# NRF52_Metal_Detector_v1_0.net
KiCad netlist of a schematic drawn in EAGLE
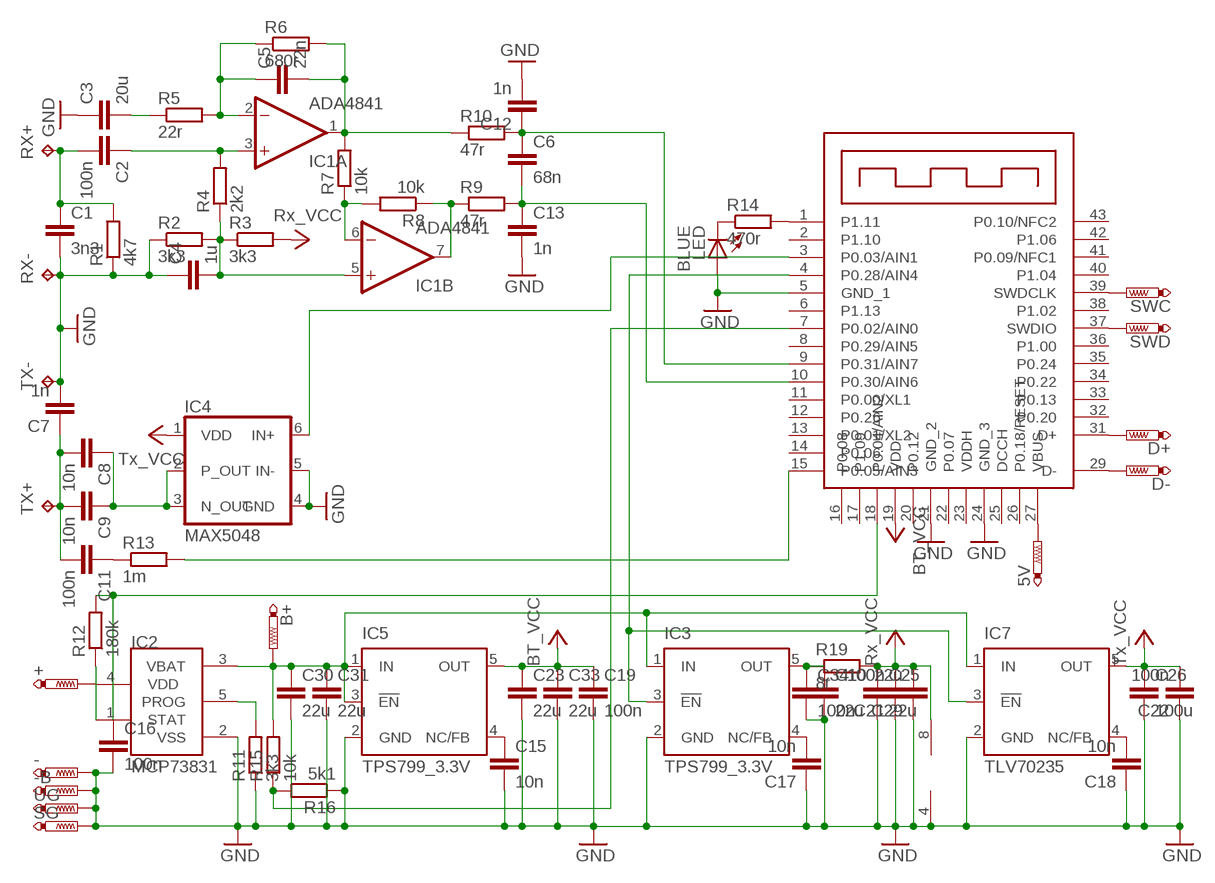
[diagram p0: schematic, sheet 1]

(export (version "E")
  (design (tool "Eeschema 10.0.6"))
  (components
    (comp (ref "+")
      (value "PTR1TP20SQ")
      (footprint "eagle-import:TP20SQ")
      (libsource (lib "eagle-import") (part "PTR1TP20SQ"))
    )
    (comp (ref "-")
      (value "PTR1TP20SQ")
      (footprint "eagle-import:TP20SQ")
      (libsource (lib "eagle-import") (part "PTR1TP20SQ"))
    )
    (comp (ref "-B")
      (value "PTR1TP20SQ")
      (footprint "eagle-import:TP20SQ")
      (libsource (lib "eagle-import") (part "PTR1TP20SQ"))
    )
    (comp (ref "5V")
      (value "PTR1TP13SQ")
      (footprint "eagle-import:TP13SQ")
      (libsource (lib "eagle-import") (part "PTR1TP13SQ"))
    )
    (comp (ref "B+")
      (value "PTR1TP20SQ")
      (footprint "eagle-import:TP20SQ")
      (libsource (lib "eagle-import") (part "PTR1TP20SQ"))
    )
    (comp (ref "C1")
      (value "3n3")
      (footprint "eagle-import:C0805")
      (libsource (lib "eagle-import") (part "C-EUC0805"))
    )
    (comp (ref "C2")
      (value "100n")
      (footprint "eagle-import:C1206")
      (libsource (lib "eagle-import") (part "C-EUC1206"))
    )
    (comp (ref "C3")
      (value "20u")
      (footprint "eagle-import:C1206")
      (libsource (lib "eagle-import") (part "C-EUC1206"))
    )
    (comp (ref "C4")
      (value "1u")
      (footprint "eagle-import:C1206")
      (libsource (lib "eagle-import") (part "C-EUC1206"))
    )
    (comp (ref "C5")
      (value "22n")
      (footprint "eagle-import:C0805")
      (libsource (lib "eagle-import") (part "C-EUC0805"))
    )
    (comp (ref "C6")
      (value "68n")
      (footprint "eagle-import:C1206")
      (libsource (lib "eagle-import") (part "C-EUC1206"))
    )
    (comp (ref "C7")
      (value "1n")
      (footprint "eagle-import:C0805")
      (libsource (lib "eagle-import") (part "C-EUC0805"))
    )
    (comp (ref "C8")
      (value "10n")
      (footprint "eagle-import:C1206")
      (libsource (lib "eagle-import") (part "C-EUC1206"))
    )
    (comp (ref "C9")
      (value "10n")
      (footprint "eagle-import:C1206")
      (libsource (lib "eagle-import") (part "C-EUC1206"))
    )
    (comp (ref "C10")
      (value "22u")
      (footprint "eagle-import:C1206")
      (libsource (lib "eagle-import") (part "C-EUC1206"))
    )
    (comp (ref "C11")
      (value "100n")
      (footprint "eagle-import:C1206")
      (libsource (lib "eagle-import") (part "C-EUC1206"))
    )
    (comp (ref "C12")
      (value "1n")
      (footprint "eagle-import:C0805")
      (libsource (lib "eagle-import") (part "C-EUC0805"))
    )
    (comp (ref "C13")
      (value "1n")
      (footprint "eagle-import:C0805")
      (libsource (lib "eagle-import") (part "C-EUC0805"))
    )
    (comp (ref "C15")
      (value "10n")
      (footprint "eagle-import:C0805")
      (libsource (lib "eagle-import") (part "C-EUC0805"))
    )
    (comp (ref "C16")
      (value "100n")
      (footprint "eagle-import:C0805")
      (libsource (lib "eagle-import") (part "C-EUC0805"))
    )
    (comp (ref "C17")
      (value "10n")
      (footprint "eagle-import:C0805")
      (libsource (lib "eagle-import") (part "C-EUC0805"))
    )
    (comp (ref "C18")
      (value "10n")
      (footprint "eagle-import:C0805")
      (libsource (lib "eagle-import") (part "C-EUC0805"))
    )
    (comp (ref "C19")
      (value "100n")
      (footprint "eagle-import:C0805")
      (libsource (lib "eagle-import") (part "C-EUC0805"))
    )
    (comp (ref "C21")
      (value "100n")
      (footprint "eagle-import:C0805")
      (libsource (lib "eagle-import") (part "C-EUC0805"))
    )
    (comp (ref "C22")
      (value "100n")
      (footprint "eagle-import:C0805")
      (libsource (lib "eagle-import") (part "C-EUC0805"))
    )
    (comp (ref "C23")
      (value "22u")
      (footprint "eagle-import:C1206")
      (libsource (lib "eagle-import") (part "C-EUC1206"))
    )
    (comp (ref "C25")
      (value "22u")
      (footprint "eagle-import:C1206")
      (libsource (lib "eagle-import") (part "C-EUC1206"))
    )
    (comp (ref "C26")
      (value "100u")
      (footprint "eagle-import:C1206")
      (libsource (lib "eagle-import") (part "C-EUC1206"))
    )
    (comp (ref "C29")
      (value "22u")
      (footprint "eagle-import:C1206")
      (libsource (lib "eagle-import") (part "C-EUC1206"))
    )
    (comp (ref "C30")
      (value "22u")
      (footprint "eagle-import:C1206")
      (libsource (lib "eagle-import") (part "C-EUC1206"))
    )
    (comp (ref "C31")
      (value "22u")
      (footprint "eagle-import:C1206")
      (libsource (lib "eagle-import") (part "C-EUC1206"))
    )
    (comp (ref "C33")
      (value "22u")
      (footprint "eagle-import:C1206")
      (libsource (lib "eagle-import") (part "C-EUC1206"))
    )
    (comp (ref "C34")
      (value "100n")
      (footprint "eagle-import:C0805")
      (libsource (lib "eagle-import") (part "C-EUC0805"))
    )
    (comp (ref "D+")
      (value "PTR1TP13SQ")
      (footprint "eagle-import:TP13SQ")
      (libsource (lib "eagle-import") (part "PTR1TP13SQ"))
    )
    (comp (ref "D-")
      (value "PTR1TP13SQ")
      (footprint "eagle-import:TP13SQ")
      (libsource (lib "eagle-import") (part "PTR1TP13SQ"))
    )
    (comp (ref "E73-2G4M08S1C1")
      (value "E73-2G4M08S1C")
      (footprint "eagle-import:E73-2G4M08S1C")
      (libsource (lib "eagle-import") (part "E73-2G4M08S1C"))
    )
    (comp (ref "IC1")
      (value "ADA4841")
      (footprint "eagle-import:SO08")
      (libsource (lib "eagle-import") (part "LM393D"))
    )
    (comp (ref "IC2")
      (value "MCP73831")
      (footprint "eagle-import:SOT23-5L")
      (libsource (lib "eagle-import") (part "MCP73831"))
    )
    (comp (ref "IC3")
      (value "TPS799_3.3V")
      (footprint "eagle-import:SOT23-DBV")
      (fields (field (name "MF") "TEXAS INSTRUMENTS") (field (name "MPN") "TPS77001DBVT"))
      (libsource (lib "eagle-import") (part "TPS77001"))
    )
    (comp (ref "IC4")
      (value "MAX5048")
      (footprint "eagle-import:SOT23-6")
      (libsource (lib "eagle-import") (part "MAX5048"))
    )
    (comp (ref "IC5")
      (value "TPS799_3.3V")
      (footprint "eagle-import:SOT23-DBV")
      (fields (field (name "MF") "TEXAS INSTRUMENTS") (field (name "MPN") "TPS77001DBVT"))
      (libsource (lib "eagle-import") (part "TPS77001"))
    )
    (comp (ref "IC7")
      (value "TLV70235")
      (footprint "eagle-import:SOT23-DBV")
      (fields (field (name "MF") "TEXAS INSTRUMENTS") (field (name "MPN") "TPS77001DBVT"))
      (libsource (lib "eagle-import") (part "TPS77001"))
    )
    (comp (ref "LED")
      (value "BLUE")
      (footprint "eagle-import:SML0805")
      (libsource (lib "eagle-import") (part "LEDSML0805"))
    )
    (comp (ref "R1")
      (value "4k7")
      (footprint "eagle-import:R0805")
      (libsource (lib "eagle-import") (part "R-EU_R0805"))
    )
    (comp (ref "R2")
      (value "3k3")
      (footprint "eagle-import:R0805")
      (libsource (lib "eagle-import") (part "R-EU_R0805"))
    )
    (comp (ref "R3")
      (value "3k3")
      (footprint "eagle-import:R0805")
      (libsource (lib "eagle-import") (part "R-EU_R0805"))
    )
    (comp (ref "R4")
      (value "2k2")
      (footprint "eagle-import:R0805")
      (libsource (lib "eagle-import") (part "R-EU_R0805"))
    )
    (comp (ref "R5")
      (value "22r")
      (footprint "eagle-import:R0805")
      (libsource (lib "eagle-import") (part "R-EU_R0805"))
    )
    (comp (ref "R6")
      (value "680r")
      (footprint "eagle-import:R0805")
      (libsource (lib "eagle-import") (part "R-EU_R0805"))
    )
    (comp (ref "R7")
      (value "10k")
      (footprint "eagle-import:R0805")
      (libsource (lib "eagle-import") (part "R-EU_R0805"))
    )
    (comp (ref "R8")
      (value "10k")
      (footprint "eagle-import:R0805")
      (libsource (lib "eagle-import") (part "R-EU_R0805"))
    )
    (comp (ref "R9")
      (value "47r")
      (footprint "eagle-import:R0805")
      (libsource (lib "eagle-import") (part "R-EU_R0805"))
    )
    (comp (ref "R10")
      (value "47r")
      (footprint "eagle-import:R0805")
      (libsource (lib "eagle-import") (part "R-EU_R0805"))
    )
    (comp (ref "R11")
      (value "3k3")
      (footprint "eagle-import:R0805")
      (libsource (lib "eagle-import") (part "R-EU_R0805"))
    )
    (comp (ref "R12")
      (value "180k")
      (footprint "eagle-import:R0805")
      (libsource (lib "eagle-import") (part "R-EU_R0805"))
    )
    (comp (ref "R13")
      (value "1m")
      (footprint "eagle-import:R0805")
      (libsource (lib "eagle-import") (part "R-EU_R0805"))
    )
    (comp (ref "R14")
      (value "470r")
      (footprint "eagle-import:R0805")
      (libsource (lib "eagle-import") (part "R-EU_R0805"))
    )
    (comp (ref "R15")
      (value "10k")
      (footprint "eagle-import:R0805")
      (libsource (lib "eagle-import") (part "R-EU_R0805"))
    )
    (comp (ref "R16")
      (value "5k1")
      (footprint "eagle-import:R0805")
      (libsource (lib "eagle-import") (part "R-EU_R0805"))
    )
    (comp (ref "R19")
      (value "8r")
      (footprint "eagle-import:R1206")
      (libsource (lib "eagle-import") (part "R-EU_R1206"))
    )
    (comp (ref "RX+")
      (value "TPPAD1-13")
      (footprint "eagle-import:P1-13")
      (libsource (lib "eagle-import") (part "TPPAD1-13"))
    )
    (comp (ref "RX-")
      (value "TPPAD1-13")
      (footprint "eagle-import:P1-13")
      (libsource (lib "eagle-import") (part "TPPAD1-13"))
    )
    (comp (ref "SG")
      (value "PTR1TP13SQ")
      (footprint "eagle-import:TP13SQ")
      (libsource (lib "eagle-import") (part "PTR1TP13SQ"))
    )
    (comp (ref "SWC")
      (value "PTR1TP13SQ")
      (footprint "eagle-import:TP13SQ")
      (libsource (lib "eagle-import") (part "PTR1TP13SQ"))
    )
    (comp (ref "SWD")
      (value "PTR1TP13SQ")
      (footprint "eagle-import:TP13SQ")
      (libsource (lib "eagle-import") (part "PTR1TP13SQ"))
    )
    (comp (ref "TX+")
      (value "TPPAD1-13")
      (footprint "eagle-import:P1-13")
      (libsource (lib "eagle-import") (part "TPPAD1-13"))
    )
    (comp (ref "TX-")
      (value "TPPAD1-13")
      (footprint "eagle-import:P1-13")
      (libsource (lib "eagle-import") (part "TPPAD1-13"))
    )
    (comp (ref "UG")
      (value "PTR1TP13SQ")
      (footprint "eagle-import:TP13SQ")
      (libsource (lib "eagle-import") (part "PTR1TP13SQ"))
    )
  )
  (nets
    (net (code "1") (name "BT_VCC") (class "Default")
      (node (ref "C19") (pin "1") (pinfunction "1_1") (pintype "passive"))
      (node (ref "C23") (pin "1") (pinfunction "1_1") (pintype "passive"))
      (node (ref "C33") (pin "1") (pinfunction "1_1") (pintype "passive"))
      (node (ref "E73-2G4M08S1C1") (pin "19") (pinfunction "VDD_19") (pintype "power_in"))
      (node (ref "IC5") (pin "5") (pinfunction "OUT_5") (pintype "passive"))
    )
    (net (code "2") (name "GND") (class "Default")
      (node (ref "-") (pin "TP") (pinfunction "TP_TP") (pintype "input"))
      (node (ref "-B") (pin "TP") (pinfunction "TP_TP") (pintype "input"))
      (node (ref "C1") (pin "2") (pinfunction "2_2") (pintype "passive"))
      (node (ref "C10") (pin "2") (pinfunction "2_2") (pintype "passive"))
      (node (ref "C12") (pin "2") (pinfunction "2_2") (pintype "passive"))
      (node (ref "C13") (pin "2") (pinfunction "2_2") (pintype "passive"))
      (node (ref "C15") (pin "2") (pinfunction "2_2") (pintype "passive"))
      (node (ref "C16") (pin "2") (pinfunction "2_2") (pintype "passive"))
      (node (ref "C17") (pin "1") (pinfunction "1_1") (pintype "passive"))
      (node (ref "C18") (pin "1") (pinfunction "1_1") (pintype "passive"))
      (node (ref "C19") (pin "2") (pinfunction "2_2") (pintype "passive"))
      (node (ref "C21") (pin "1") (pinfunction "1_1") (pintype "passive"))
      (node (ref "C22") (pin "1") (pinfunction "1_1") (pintype "passive"))
      (node (ref "C23") (pin "2") (pinfunction "2_2") (pintype "passive"))
      (node (ref "C25") (pin "2") (pinfunction "2_2") (pintype "passive"))
      (node (ref "C26") (pin "2") (pinfunction "2_2") (pintype "passive"))
      (node (ref "C29") (pin "1") (pinfunction "1_1") (pintype "passive"))
      (node (ref "C3") (pin "1") (pinfunction "1_1") (pintype "passive"))
      (node (ref "C30") (pin "2") (pinfunction "2_2") (pintype "passive"))
      (node (ref "C31") (pin "2") (pinfunction "2_2") (pintype "passive"))
      (node (ref "C33") (pin "2") (pinfunction "2_2") (pintype "passive"))
      (node (ref "C34") (pin "2") (pinfunction "2_2") (pintype "passive"))
      (node (ref "C4") (pin "1") (pinfunction "1_1") (pintype "passive"))
      (node (ref "C7") (pin "2") (pinfunction "2_2") (pintype "passive"))
      (node (ref "E73-2G4M08S1C1") (pin "21") (pinfunction "GND_2_21") (pintype "power_in"))
      (node (ref "E73-2G4M08S1C1") (pin "24") (pinfunction "GND_3_24") (pintype "power_in"))
      (node (ref "E73-2G4M08S1C1") (pin "5") (pinfunction "GND_1_5") (pintype "power_in"))
      (node (ref "IC1") (pin "4") (pinfunction "V-_4") (pintype "power_in"))
      (node (ref "IC2") (pin "2") (pinfunction "VSS_2") (pintype "bidirectional"))
      (node (ref "IC3") (pin "2") (pinfunction "GND_2") (pintype "power_in"))
      (node (ref "IC4") (pin "4") (pinfunction "GND_4") (pintype "bidirectional"))
      (node (ref "IC4") (pin "5") (pinfunction "IN-_5") (pintype "input"))
      (node (ref "IC5") (pin "2") (pinfunction "GND_2") (pintype "power_in"))
      (node (ref "IC7") (pin "2") (pinfunction "GND_2") (pintype "power_in"))
      (node (ref "LED") (pin "A") (pinfunction "A_A") (pintype "passive"))
      (node (ref "R1") (pin "1") (pinfunction "1_1") (pintype "passive"))
      (node (ref "R11") (pin "1") (pinfunction "1_1") (pintype "passive"))
      (node (ref "R16") (pin "1") (pinfunction "1_1") (pintype "passive"))
      (node (ref "R2") (pin "1") (pinfunction "1_1") (pintype "passive"))
      (node (ref "RX-") (pin "TP") (pinfunction "TP_TP") (pintype "input"))
      (node (ref "SG") (pin "TP") (pinfunction "TP_TP") (pintype "input"))
      (node (ref "TX-") (pin "TP") (pinfunction "TP_TP") (pintype "input"))
      (node (ref "UG") (pin "TP") (pinfunction "TP_TP") (pintype "input"))
    )
    (net (code "3") (name "Net-(C1-Pad1)") (class "Default")
      (node (ref "C1") (pin "1") (pinfunction "1_1") (pintype "passive"))
      (node (ref "C2") (pin "2") (pinfunction "2_2") (pintype "passive"))
      (node (ref "R1") (pin "2") (pinfunction "2_2") (pintype "passive"))
      (node (ref "RX+") (pin "TP") (pinfunction "TP_TP") (pintype "input"))
    )
    (net (code "4") (name "Net-(C3-Pad2)") (class "Default")
      (node (ref "C3") (pin "2") (pinfunction "2_2") (pintype "passive"))
      (node (ref "R5") (pin "1") (pinfunction "1_1") (pintype "passive"))
    )
    (net (code "5") (name "Net-(C11-Pad1)") (class "Default")
      (node (ref "C11") (pin "1") (pinfunction "1_1") (pintype "passive"))
      (node (ref "R13") (pin "1") (pinfunction "1_1") (pintype "passive"))
    )
    (net (code "6") (name "Net-(C11-Pad2)") (class "Default")
      (node (ref "C11") (pin "2") (pinfunction "2_2") (pintype "passive"))
      (node (ref "C7") (pin "1") (pinfunction "1_1") (pintype "passive"))
      (node (ref "C8") (pin "2") (pinfunction "2_2") (pintype "passive"))
      (node (ref "C9") (pin "2") (pinfunction "2_2") (pintype "passive"))
      (node (ref "TX+") (pin "TP") (pinfunction "TP_TP") (pintype "input"))
    )
    (net (code "7") (name "Net-(E73-2G4M08S1C1-D+)") (class "Default")
      (node (ref "D+") (pin "TP") (pinfunction "TP_TP") (pintype "input"))
      (node (ref "E73-2G4M08S1C1") (pin "31") (pinfunction "D+_31") (pintype "bidirectional"))
    )
    (net (code "8") (name "Net-(E73-2G4M08S1C1-D-)") (class "Default")
      (node (ref "D-") (pin "TP") (pinfunction "TP_TP") (pintype "input"))
      (node (ref "E73-2G4M08S1C1") (pin "29") (pinfunction "D-_29") (pintype "bidirectional"))
    )
    (net (code "9") (name "Net-(E73-2G4M08S1C1-P0.02{slash}AIN0)") (class "Default")
      (node (ref "E73-2G4M08S1C1") (pin "7") (pinfunction "P0.02/AIN0_7") (pintype "bidirectional"))
      (node (ref "R15") (pin "1") (pinfunction "1_1") (pintype "passive"))
      (node (ref "R16") (pin "2") (pinfunction "2_2") (pintype "passive"))
    )
    (net (code "10") (name "Net-(E73-2G4M08S1C1-P0.03{slash}AIN1)") (class "Default")
      (node (ref "E73-2G4M08S1C1") (pin "3") (pinfunction "P0.03/AIN1_3") (pintype "bidirectional"))
      (node (ref "IC4") (pin "6") (pinfunction "IN+_6") (pintype "input"))
    )
    (net (code "11") (name "Net-(E73-2G4M08S1C1-P0.04{slash}AIN2)") (class "Default")
      (node (ref "C16") (pin "1") (pinfunction "1_1") (pintype "passive"))
      (node (ref "E73-2G4M08S1C1") (pin "18") (pinfunction "P0.04/AIN2_18") (pintype "bidirectional"))
      (node (ref "R12") (pin "2") (pinfunction "2_2") (pintype "passive"))
    )
    (net (code "12") (name "Net-(E73-2G4M08S1C1-P0.05{slash}AIN3)") (class "Default")
      (node (ref "E73-2G4M08S1C1") (pin "15") (pinfunction "P0.05/AIN3_15") (pintype "bidirectional"))
      (node (ref "R13") (pin "2") (pinfunction "2_2") (pintype "passive"))
    )
    (net (code "13") (name "Net-(E73-2G4M08S1C1-P0.28{slash}AIN4)") (class "Default")
      (node (ref "E73-2G4M08S1C1") (pin "4") (pinfunction "P0.28/AIN4_4") (pintype "bidirectional"))
      (node (ref "IC3") (pin "3") (pinfunction "~{EN}_3") (pintype "input"))
      (node (ref "IC7") (pin "3") (pinfunction "~{EN}_3") (pintype "input"))
    )
    (net (code "14") (name "Net-(E73-2G4M08S1C1-P0.30{slash}AIN6)") (class "Default")
      (node (ref "C13") (pin "1") (pinfunction "1_1") (pintype "passive"))
      (node (ref "C6") (pin "2") (pinfunction "2_2") (pintype "passive"))
      (node (ref "E73-2G4M08S1C1") (pin "10") (pinfunction "P0.30/AIN6_10") (pintype "bidirectional"))
      (node (ref "R9") (pin "2") (pinfunction "2_2") (pintype "passive"))
    )
    (net (code "15") (name "Net-(E73-2G4M08S1C1-P0.31{slash}AIN7)") (class "Default")
      (node (ref "C12") (pin "1") (pinfunction "1_1") (pintype "passive"))
      (node (ref "C6") (pin "1") (pinfunction "1_1") (pintype "passive"))
      (node (ref "E73-2G4M08S1C1") (pin "9") (pinfunction "P0.31/AIN7_9") (pintype "bidirectional"))
      (node (ref "R10") (pin "2") (pinfunction "2_2") (pintype "passive"))
    )
    (net (code "16") (name "Net-(E73-2G4M08S1C1-P1.11)") (class "Default")
      (node (ref "E73-2G4M08S1C1") (pin "1") (pinfunction "P1.11_1") (pintype "bidirectional"))
      (node (ref "R14") (pin "2") (pinfunction "2_2") (pintype "passive"))
    )
    (net (code "17") (name "Net-(E73-2G4M08S1C1-SWDCLK)") (class "Default")
      (node (ref "E73-2G4M08S1C1") (pin "39") (pinfunction "SWDCLK_39") (pintype "bidirectional"))
      (node (ref "SWC") (pin "TP") (pinfunction "TP_TP") (pintype "input"))
    )
    (net (code "18") (name "Net-(E73-2G4M08S1C1-SWDIO)") (class "Default")
      (node (ref "E73-2G4M08S1C1") (pin "37") (pinfunction "SWDIO_37") (pintype "bidirectional"))
      (node (ref "SWD") (pin "TP") (pinfunction "TP_TP") (pintype "input"))
    )
    (net (code "19") (name "Net-(E73-2G4M08S1C1-VBUS)") (class "Default")
      (node (ref "5V") (pin "TP") (pinfunction "TP_TP") (pintype "input"))
      (node (ref "E73-2G4M08S1C1") (pin "27") (pinfunction "VBUS_27") (pintype "bidirectional"))
    )
    (net (code "20") (name "Net-(IC1A-+IN)") (class "Default")
      (node (ref "C2") (pin "1") (pinfunction "1_1") (pintype "passive"))
      (node (ref "IC1") (pin "3") (pinfunction "+IN_3") (pintype "input"))
      (node (ref "R4") (pin "2") (pinfunction "2_2") (pintype "passive"))
    )
    (net (code "21") (name "Net-(IC1A--IN)") (class "Default")
      (node (ref "C5") (pin "1") (pinfunction "1_1") (pintype "passive"))
      (node (ref "IC1") (pin "2") (pinfunction "-IN_2") (pintype "input"))
      (node (ref "R5") (pin "2") (pinfunction "2_2") (pintype "passive"))
      (node (ref "R6") (pin "1") (pinfunction "1_1") (pintype "passive"))
    )
    (net (code "22") (name "Net-(IC1A-OUT)") (class "Default")
      (node (ref "C5") (pin "2") (pinfunction "2_2") (pintype "passive"))
      (node (ref "IC1") (pin "1") (pinfunction "OUT_1") (pintype "output"))
      (node (ref "R10") (pin "1") (pinfunction "1_1") (pintype "passive"))
      (node (ref "R6") (pin "2") (pinfunction "2_2") (pintype "passive"))
      (node (ref "R7") (pin "2") (pinfunction "2_2") (pintype "passive"))
    )
    (net (code "23") (name "Net-(IC1B-+IN)") (class "Default")
      (node (ref "C4") (pin "2") (pinfunction "2_2") (pintype "passive"))
      (node (ref "IC1") (pin "5") (pinfunction "+IN_5") (pintype "input"))
      (node (ref "R2") (pin "2") (pinfunction "2_2") (pintype "passive"))
      (node (ref "R3") (pin "1") (pinfunction "1_1") (pintype "passive"))
      (node (ref "R4") (pin "1") (pinfunction "1_1") (pintype "passive"))
    )
    (net (code "24") (name "Net-(IC1B--IN)") (class "Default")
      (node (ref "IC1") (pin "6") (pinfunction "-IN_6") (pintype "input"))
      (node (ref "R7") (pin "1") (pinfunction "1_1") (pintype "passive"))
      (node (ref "R8") (pin "2") (pinfunction "2_2") (pintype "passive"))
    )
    (net (code "25") (name "Net-(IC1B-OUT)") (class "Default")
      (node (ref "IC1") (pin "7") (pinfunction "OUT_7") (pintype "output"))
      (node (ref "R8") (pin "1") (pinfunction "1_1") (pintype "passive"))
      (node (ref "R9") (pin "1") (pinfunction "1_1") (pintype "passive"))
    )
    (net (code "26") (name "Net-(IC2-PROG)") (class "Default")
      (node (ref "IC2") (pin "5") (pinfunction "PROG_5") (pintype "bidirectional"))
      (node (ref "R11") (pin "2") (pinfunction "2_2") (pintype "passive"))
    )
    (net (code "27") (name "Net-(IC2-STAT)") (class "Default")
      (node (ref "IC2") (pin "1") (pinfunction "STAT_1") (pintype "bidirectional"))
      (node (ref "R12") (pin "1") (pinfunction "1_1") (pintype "passive"))
    )
    (net (code "28") (name "Net-(IC2-VBAT)") (class "Default")
      (node (ref "B+") (pin "TP") (pinfunction "TP_TP") (pintype "input"))
      (node (ref "C30") (pin "1") (pinfunction "1_1") (pintype "passive"))
      (node (ref "C31") (pin "1") (pinfunction "1_1") (pintype "passive"))
      (node (ref "IC2") (pin "3") (pinfunction "VBAT_3") (pintype "bidirectional"))
      (node (ref "IC3") (pin "1") (pinfunction "IN_1") (pintype "input"))
      (node (ref "IC5") (pin "1") (pinfunction "IN_1") (pintype "input"))
      (node (ref "IC5") (pin "3") (pinfunction "~{EN}_3") (pintype "input"))
      (node (ref "IC7") (pin "1") (pinfunction "IN_1") (pintype "input"))
      (node (ref "R15") (pin "2") (pinfunction "2_2") (pintype "passive"))
    )
    (net (code "29") (name "Net-(IC2-VDD)") (class "Default")
      (node (ref "+") (pin "TP") (pinfunction "TP_TP") (pintype "input"))
      (node (ref "IC2") (pin "4") (pinfunction "VDD_4") (pintype "bidirectional"))
    )
    (net (code "30") (name "Net-(IC3-NC{slash}FB)") (class "Default")
      (node (ref "C17") (pin "2") (pinfunction "2_2") (pintype "passive"))
      (node (ref "IC3") (pin "4") (pinfunction "NC/FB_4") (pintype "passive"))
    )
    (net (code "31") (name "Net-(IC3-OUT)") (class "Default")
      (node (ref "C10") (pin "1") (pinfunction "1_1") (pintype "passive"))
      (node (ref "C34") (pin "1") (pinfunction "1_1") (pintype "passive"))
      (node (ref "IC3") (pin "5") (pinfunction "OUT_5") (pintype "passive"))
      (node (ref "R19") (pin "1") (pinfunction "1_1") (pintype "passive"))
    )
    (net (code "32") (name "Net-(IC4-N_OUT)") (class "Default")
      (node (ref "C8") (pin "1") (pinfunction "1_1") (pintype "passive"))
      (node (ref "C9") (pin "1") (pinfunction "1_1") (pintype "passive"))
      (node (ref "IC4") (pin "2") (pinfunction "P_OUT_2") (pintype "output"))
      (node (ref "IC4") (pin "3") (pinfunction "N_OUT_3") (pintype "output"))
    )
    (net (code "33") (name "Net-(IC5-NC{slash}FB)") (class "Default")
      (node (ref "C15") (pin "1") (pinfunction "1_1") (pintype "passive"))
      (node (ref "IC5") (pin "4") (pinfunction "NC/FB_4") (pintype "passive"))
    )
    (net (code "34") (name "Net-(IC7-NC{slash}FB)") (class "Default")
      (node (ref "C18") (pin "2") (pinfunction "2_2") (pintype "passive"))
      (node (ref "IC7") (pin "4") (pinfunction "NC/FB_4") (pintype "passive"))
    )
    (net (code "35") (name "Net-(LED-PadC)") (class "Default")
      (node (ref "LED") (pin "C") (pinfunction "C_C") (pintype "passive"))
      (node (ref "R14") (pin "1") (pinfunction "1_1") (pintype "passive"))
    )
    (net (code "36") (name "Rx_VCC") (class "Default")
      (node (ref "C21") (pin "2") (pinfunction "2_2") (pintype "passive"))
      (node (ref "C25") (pin "1") (pinfunction "1_1") (pintype "passive"))
      (node (ref "C29") (pin "2") (pinfunction "2_2") (pintype "passive"))
      (node (ref "IC1") (pin "8") (pinfunction "V+_8") (pintype "power_in"))
      (node (ref "R19") (pin "2") (pinfunction "2_2") (pintype "passive"))
      (node (ref "R3") (pin "2") (pinfunction "2_2") (pintype "passive"))
    )
    (net (code "37") (name "Tx_VCC") (class "Default")
      (node (ref "C22") (pin "2") (pinfunction "2_2") (pintype "passive"))
      (node (ref "C26") (pin "1") (pinfunction "1_1") (pintype "passive"))
      (node (ref "IC4") (pin "1") (pinfunction "VDD_1") (pintype "power_in"))
      (node (ref "IC7") (pin "5") (pinfunction "OUT_5") (pintype "passive"))
    )
    (net (code "38") (name "unconnected-(E73-2G4M08S1C1-DCCH-Pad25)") (class "Default")
      (node (ref "E73-2G4M08S1C1") (pin "25") (pinfunction "DCCH_25") (pintype "bidirectional"))
    )
    (net (code "39") (name "unconnected-(E73-2G4M08S1C1-P0.00{slash}XL1-Pad11)") (class "Default")
      (node (ref "E73-2G4M08S1C1") (pin "11") (pinfunction "P0.00/XL1_11") (pintype "bidirectional"))
    )
    (net (code "40") (name "unconnected-(E73-2G4M08S1C1-P0.01{slash}XL2-Pad13)") (class "Default")
      (node (ref "E73-2G4M08S1C1") (pin "13") (pinfunction "P0.01/XL2_13") (pintype "bidirectional"))
    )
    (net (code "41") (name "unconnected-(E73-2G4M08S1C1-P0.06-Pad14)") (class "Default")
      (node (ref "E73-2G4M08S1C1") (pin "14") (pinfunction "P0.06_14") (pintype "bidirectional"))
    )
    (net (code "42") (name "unconnected-(E73-2G4M08S1C1-P0.07-Pad22)") (class "Default")
      (node (ref "E73-2G4M08S1C1") (pin "22") (pinfunction "P0.07_22") (pintype "bidirectional"))
    )
    (net (code "43") (name "unconnected-(E73-2G4M08S1C1-P0.08-Pad16)") (class "Default")
      (node (ref "E73-2G4M08S1C1") (pin "16") (pinfunction "P0.08_16") (pintype "bidirectional"))
    )
    (net (code "44") (name "unconnected-(E73-2G4M08S1C1-P0.09{slash}NFC1-Pad41)") (class "Default")
      (node (ref "E73-2G4M08S1C1") (pin "41") (pinfunction "P0.09/NFC1_41") (pintype "bidirectional"))
    )
    (net (code "45") (name "unconnected-(E73-2G4M08S1C1-P0.10{slash}NFC2-Pad43)") (class "Default")
      (node (ref "E73-2G4M08S1C1") (pin "43") (pinfunction "P0.10/NFC2_43") (pintype "bidirectional"))
    )
    (net (code "46") (name "unconnected-(E73-2G4M08S1C1-P0.12-Pad20)") (class "Default")
      (node (ref "E73-2G4M08S1C1") (pin "20") (pinfunction "P0.12_20") (pintype "bidirectional"))
    )
    (net (code "47") (name "unconnected-(E73-2G4M08S1C1-P0.13-Pad33)") (class "Default")
      (node (ref "E73-2G4M08S1C1") (pin "33") (pinfunction "P0.13_33") (pintype "bidirectional"))
    )
    (net (code "48") (name "unconnected-(E73-2G4M08S1C1-P0.18{slash}RESET-Pad26)") (class "Default")
      (node (ref "E73-2G4M08S1C1") (pin "26") (pinfunction "P0.18/RESET_26") (pintype "bidirectional"))
    )
    (net (code "49") (name "unconnected-(E73-2G4M08S1C1-P0.20-Pad32)") (class "Default")
      (node (ref "E73-2G4M08S1C1") (pin "32") (pinfunction "P0.20_32") (pintype "bidirectional"))
    )
    (net (code "50") (name "unconnected-(E73-2G4M08S1C1-P0.22-Pad34)") (class "Default")
      (node (ref "E73-2G4M08S1C1") (pin "34") (pinfunction "P0.22_34") (pintype "bidirectional"))
    )
    (net (code "51") (name "unconnected-(E73-2G4M08S1C1-P0.24-Pad35)") (class "Default")
      (node (ref "E73-2G4M08S1C1") (pin "35") (pinfunction "P0.24_35") (pintype "bidirectional"))
    )
    (net (code "52") (name "unconnected-(E73-2G4M08S1C1-P0.26-Pad12)") (class "Default")
      (node (ref "E73-2G4M08S1C1") (pin "12") (pinfunction "P0.26_12") (pintype "bidirectional"))
    )
    (net (code "53") (name "unconnected-(E73-2G4M08S1C1-P0.29{slash}AIN5-Pad8)") (class "Default")
      (node (ref "E73-2G4M08S1C1") (pin "8") (pinfunction "P0.29/AIN5_8") (pintype "bidirectional"))
    )
    (net (code "54") (name "unconnected-(E73-2G4M08S1C1-P1.00-Pad36)") (class "Default")
      (node (ref "E73-2G4M08S1C1") (pin "36") (pinfunction "P1.00_36") (pintype "bidirectional"))
    )
    (net (code "55") (name "unconnected-(E73-2G4M08S1C1-P1.02-Pad38)") (class "Default")
      (node (ref "E73-2G4M08S1C1") (pin "38") (pinfunction "P1.02_38") (pintype "bidirectional"))
    )
    (net (code "56") (name "unconnected-(E73-2G4M08S1C1-P1.04-Pad40)") (class "Default")
      (node (ref "E73-2G4M08S1C1") (pin "40") (pinfunction "P1.04_40") (pintype "bidirectional"))
    )
    (net (code "57") (name "unconnected-(E73-2G4M08S1C1-P1.06-Pad42)") (class "Default")
      (node (ref "E73-2G4M08S1C1") (pin "42") (pinfunction "P1.06_42") (pintype "bidirectional"))
    )
    (net (code "58") (name "unconnected-(E73-2G4M08S1C1-P1.09-Pad17)") (class "Default")
      (node (ref "E73-2G4M08S1C1") (pin "17") (pinfunction "P1.09_17") (pintype "bidirectional"))
    )
    (net (code "59") (name "unconnected-(E73-2G4M08S1C1-P1.10-Pad2)") (class "Default")
      (node (ref "E73-2G4M08S1C1") (pin "2") (pinfunction "P1.10_2") (pintype "bidirectional"))
    )
    (net (code "60") (name "unconnected-(E73-2G4M08S1C1-P1.13-Pad6)") (class "Default")
      (node (ref "E73-2G4M08S1C1") (pin "6") (pinfunction "P1.13_6") (pintype "bidirectional"))
    )
    (net (code "61") (name "unconnected-(E73-2G4M08S1C1-VDDH-Pad23)") (class "Default")
      (node (ref "E73-2G4M08S1C1") (pin "23") (pinfunction "VDDH_23") (pintype "bidirectional"))
    )
  )
)
